# TopLevel.net
KiCad netlist of a schematic drawn in Altium Designer
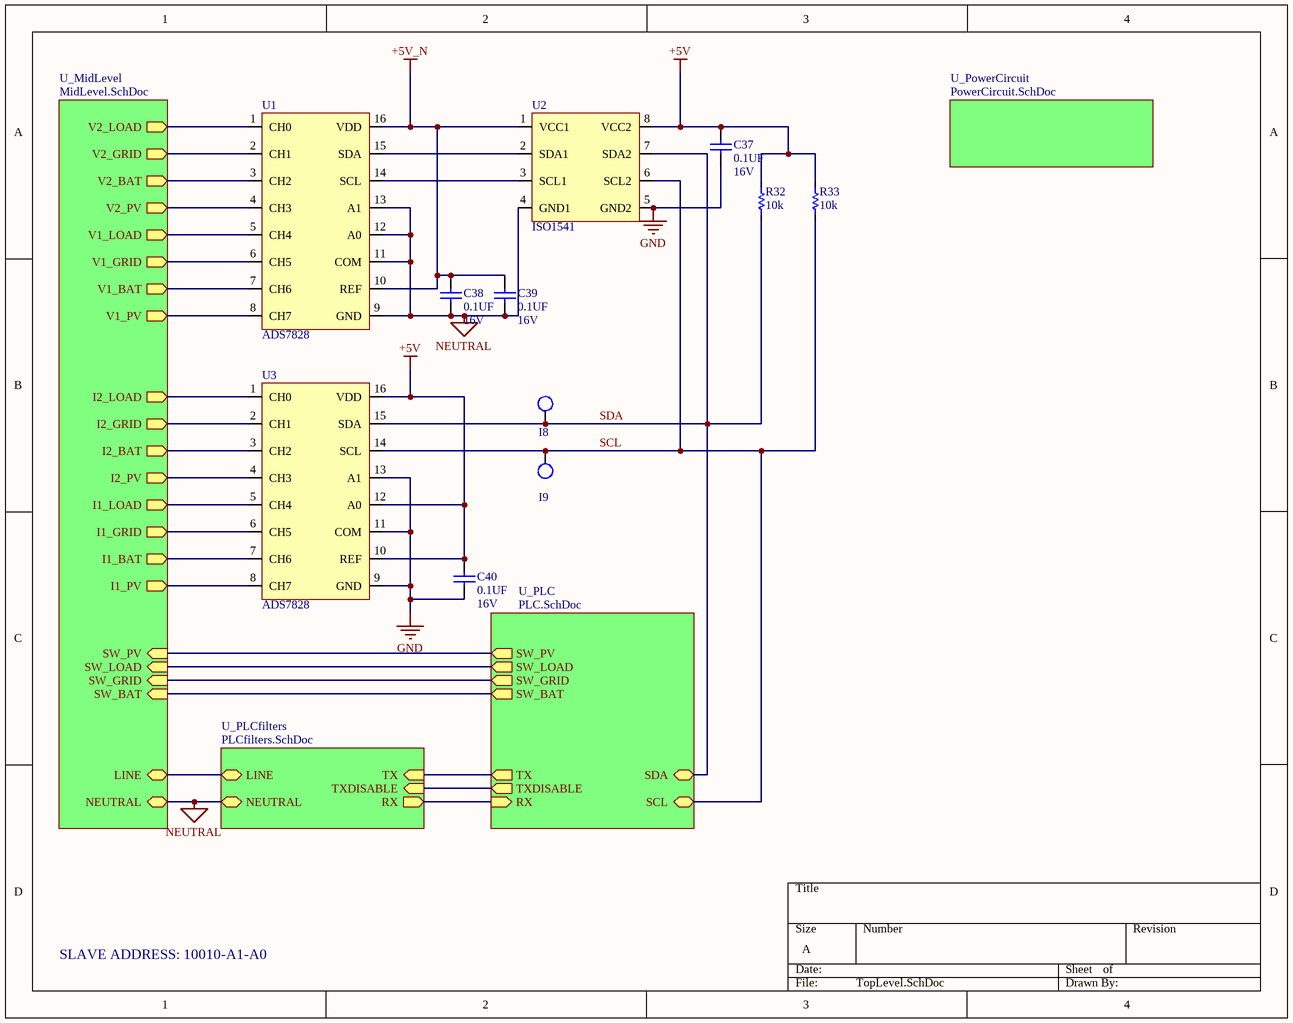
[diagram p0: TopLevel.SchDoc]

(export (version "E")
  (design (tool "Eeschema 10.0.6"))
  (components
    (comp (ref "C37")
      (value "GRM188R71C104KA01D")
      (footprint "CAPC1608X08N")
      (description "CAP CER 0.1UF 16V X7R 0603")
      (fields
        (field (name "MANUFACTURER") "Murata Electronics North America")
        (field (name "CAPACITANCE") "0.1UF")
        (field (name "VOLTAGE - RATED") "16V")
      )
      (libsource (lib "IntelligentJunctionBox") (part "GRM188R71C104KA01D"))
    )
    (comp (ref "C38")
      (value "GRM188R71C104KA01D")
      (footprint "CAPC1608X08N")
      (description "CAP CER 0.1UF 16V X7R 0603")
      (fields
        (field (name "MANUFACTURER") "Murata Electronics North America")
        (field (name "CAPACITANCE") "0.1UF")
        (field (name "VOLTAGE - RATED") "16V")
      )
      (libsource (lib "IntelligentJunctionBox") (part "GRM188R71C104KA01D"))
    )
    (comp (ref "C39")
      (value "GRM188R71C104KA01D")
      (footprint "CAPC1608X08N")
      (description "CAP CER 0.1UF 16V X7R 0603")
      (fields
        (field (name "MANUFACTURER") "Murata Electronics North America")
        (field (name "CAPACITANCE") "0.1UF")
        (field (name "VOLTAGE - RATED") "16V")
      )
      (libsource (lib "IntelligentJunctionBox") (part "GRM188R71C104KA01D"))
    )
    (comp (ref "C40")
      (value "GRM188R71C104KA01D")
      (footprint "CAPC1608X08N")
      (description "CAP CER 0.1UF 16V X7R 0603")
      (fields
        (field (name "MANUFACTURER") "Murata Electronics North America")
        (field (name "CAPACITANCE") "0.1UF")
        (field (name "VOLTAGE - RATED") "16V")
      )
      (libsource (lib "IntelligentJunctionBox") (part "GRM188R71C104KA01D"))
    )
    (comp (ref "I8")
      (value "Testpoint")
      (footprint "Testpoint")
      (libsource (lib "IntelligentJunctionBox") (part "Testpoint"))
    )
    (comp (ref "I9")
      (value "Testpoint")
      (footprint "Testpoint")
      (libsource (lib "IntelligentJunctionBox") (part "Testpoint"))
    )
    (comp (ref "R32")
      (value "RC0603FR-0710KL")
      (footprint "RESC1608X06N")
      (description "RES SMD 10K OHM 1% 1/10W 0603")
      (fields (field (name "MANUFACTURER") "Yageo") (field (name "RESISTANCE") "10k"))
      (libsource (lib "IntelligentJunctionBox") (part "RC0603FR-0710KL"))
    )
    (comp (ref "R33")
      (value "RC0603FR-0710KL")
      (footprint "RESC1608X06N")
      (description "RES SMD 10K OHM 1% 1/10W 0603")
      (fields (field (name "MANUFACTURER") "Yageo") (field (name "RESISTANCE") "10k"))
      (libsource (lib "IntelligentJunctionBox") (part "RC0603FR-0710KL"))
    )
    (comp (ref "U1")
      (value "ADS7828")
      (footprint "TSOP65P640X120-16N")
      (description "IC ADC 12BIT 50KSPS 8CH 16-TSSOP")
      (fields (field (name "MANUFACTURER") "Texas Instruments"))
      (libsource (lib "IntelligentJunctionBox") (part "ADS7828"))
    )
    (comp (ref "U2")
      (value "ISO1541")
      (footprint "SOIC127P600X175-8N")
      (description "DGTL ISO 2.5KV 2CH I2C 8SOIC")
      (fields (field (name "MANUFACTURER") "Texas Instruments"))
      (libsource (lib "IntelligentJunctionBox") (part "ISO1541"))
    )
    (comp (ref "U3")
      (value "ADS7828")
      (footprint "TSOP65P640X120-16N")
      (description "IC ADC 12BIT 50KSPS 8CH 16-TSSOP")
      (fields (field (name "MANUFACTURER") "Texas Instruments"))
      (libsource (lib "IntelligentJunctionBox") (part "ADS7828"))
    )
  )
  (nets
    (net (code "1") (name "+5V") (class "Default")
      (node (ref "C37") (pin "2") (pinfunction "2_2") (pintype "passive"))
      (node (ref "C40") (pin "2") (pinfunction "2_2") (pintype "passive"))
      (node (ref "R32") (pin "2") (pinfunction "2_2") (pintype "passive"))
      (node (ref "R33") (pin "2") (pinfunction "2_2") (pintype "passive"))
      (node (ref "U2") (pin "8") (pinfunction "VCC2_8") (pintype "passive"))
      (node (ref "U3") (pin "10") (pinfunction "REF_10") (pintype "passive"))
      (node (ref "U3") (pin "12") (pinfunction "A0_12") (pintype "passive"))
      (node (ref "U3") (pin "16") (pinfunction "VDD_16") (pintype "passive"))
    )
    (net (code "2") (name "+5V_N") (class "Default")
      (node (ref "C38") (pin "2") (pinfunction "2_2") (pintype "passive"))
      (node (ref "C39") (pin "2") (pinfunction "2_2") (pintype "passive"))
      (node (ref "U1") (pin "10") (pinfunction "REF_10") (pintype "passive"))
      (node (ref "U1") (pin "16") (pinfunction "VDD_16") (pintype "passive"))
      (node (ref "U2") (pin "1") (pinfunction "VCC1_1") (pintype "passive"))
    )
    (net (code "3") (name "/I1_BAT") (class "Default")
      (node (ref "U3") (pin "7") (pinfunction "CH6_7") (pintype "passive"))
    )
    (net (code "4") (name "/I1_GRID") (class "Default")
      (node (ref "U3") (pin "6") (pinfunction "CH5_6") (pintype "passive"))
    )
    (net (code "5") (name "/I1_LOAD") (class "Default")
      (node (ref "U3") (pin "5") (pinfunction "CH4_5") (pintype "passive"))
    )
    (net (code "6") (name "/I1_PV") (class "Default")
      (node (ref "U3") (pin "8") (pinfunction "CH7_8") (pintype "passive"))
    )
    (net (code "7") (name "/I2_BAT") (class "Default")
      (node (ref "U3") (pin "3") (pinfunction "CH2_3") (pintype "passive"))
    )
    (net (code "8") (name "/I2_GRID") (class "Default")
      (node (ref "U3") (pin "2") (pinfunction "CH1_2") (pintype "passive"))
    )
    (net (code "9") (name "/I2_LOAD") (class "Default")
      (node (ref "U3") (pin "1") (pinfunction "CH0_1") (pintype "passive"))
    )
    (net (code "10") (name "/I2_PV") (class "Default")
      (node (ref "U3") (pin "4") (pinfunction "CH3_4") (pintype "passive"))
    )
    (net (code "13") (name "/SCL") (class "Default")
      (node (ref "I9") (pin "1") (pinfunction "TP_1") (pintype "passive"))
      (node (ref "R33") (pin "1") (pinfunction "1_1") (pintype "passive"))
      (node (ref "U2") (pin "6") (pinfunction "SCL2_6") (pintype "passive"))
      (node (ref "U3") (pin "14") (pinfunction "SCL_14") (pintype "passive"))
    )
    (net (code "14") (name "/SDA") (class "Default")
      (node (ref "I8") (pin "1") (pinfunction "TP_1") (pintype "passive"))
      (node (ref "R32") (pin "1") (pinfunction "1_1") (pintype "passive"))
      (node (ref "U2") (pin "7") (pinfunction "SDA2_7") (pintype "passive"))
      (node (ref "U3") (pin "15") (pinfunction "SDA_15") (pintype "passive"))
    )
    (net (code "21") (name "/V1_BAT") (class "Default")
      (node (ref "U1") (pin "7") (pinfunction "CH6_7") (pintype "passive"))
    )
    (net (code "22") (name "/V1_GRID") (class "Default")
      (node (ref "U1") (pin "6") (pinfunction "CH5_6") (pintype "passive"))
    )
    (net (code "23") (name "/V1_LOAD") (class "Default")
      (node (ref "U1") (pin "5") (pinfunction "CH4_5") (pintype "passive"))
    )
    (net (code "24") (name "/V1_PV") (class "Default")
      (node (ref "U1") (pin "8") (pinfunction "CH7_8") (pintype "passive"))
    )
    (net (code "25") (name "/V2_BAT") (class "Default")
      (node (ref "U1") (pin "3") (pinfunction "CH2_3") (pintype "passive"))
    )
    (net (code "26") (name "/V2_GRID") (class "Default")
      (node (ref "U1") (pin "2") (pinfunction "CH1_2") (pintype "passive"))
    )
    (net (code "27") (name "/V2_LOAD") (class "Default")
      (node (ref "U1") (pin "1") (pinfunction "CH0_1") (pintype "passive"))
    )
    (net (code "28") (name "/V2_PV") (class "Default")
      (node (ref "U1") (pin "4") (pinfunction "CH3_4") (pintype "passive"))
    )
    (net (code "29") (name "GND") (class "Default")
      (node (ref "C37") (pin "1") (pinfunction "1_1") (pintype "passive"))
      (node (ref "C40") (pin "1") (pinfunction "1_1") (pintype "passive"))
      (node (ref "U2") (pin "5") (pinfunction "GND2_5") (pintype "passive"))
      (node (ref "U3") (pin "11") (pinfunction "COM_11") (pintype "passive"))
      (node (ref "U3") (pin "13") (pinfunction "A1_13") (pintype "passive"))
      (node (ref "U3") (pin "9") (pinfunction "GND_9") (pintype "passive"))
    )
    (net (code "30") (name "NEUTRAL") (class "Default")
      (node (ref "C38") (pin "1") (pinfunction "1_1") (pintype "passive"))
      (node (ref "C39") (pin "1") (pinfunction "1_1") (pintype "passive"))
      (node (ref "U1") (pin "11") (pinfunction "COM_11") (pintype "passive"))
      (node (ref "U1") (pin "12") (pinfunction "A0_12") (pintype "passive"))
      (node (ref "U1") (pin "13") (pinfunction "A1_13") (pintype "passive"))
      (node (ref "U1") (pin "9") (pinfunction "GND_9") (pintype "passive"))
      (node (ref "U2") (pin "4") (pinfunction "GND1_4") (pintype "passive"))
    )
    (net (code "31") (name "Net-(U1-SCL)") (class "Default")
      (node (ref "U1") (pin "14") (pinfunction "SCL_14") (pintype "passive"))
      (node (ref "U2") (pin "3") (pinfunction "SCL1_3") (pintype "passive"))
    )
    (net (code "32") (name "Net-(U1-SDA)") (class "Default")
      (node (ref "U1") (pin "15") (pinfunction "SDA_15") (pintype "passive"))
      (node (ref "U2") (pin "2") (pinfunction "SDA1_2") (pintype "passive"))
    )
  )
)
